# VRAM.net
KiCad netlist of a schematic drawn in Altium Designer
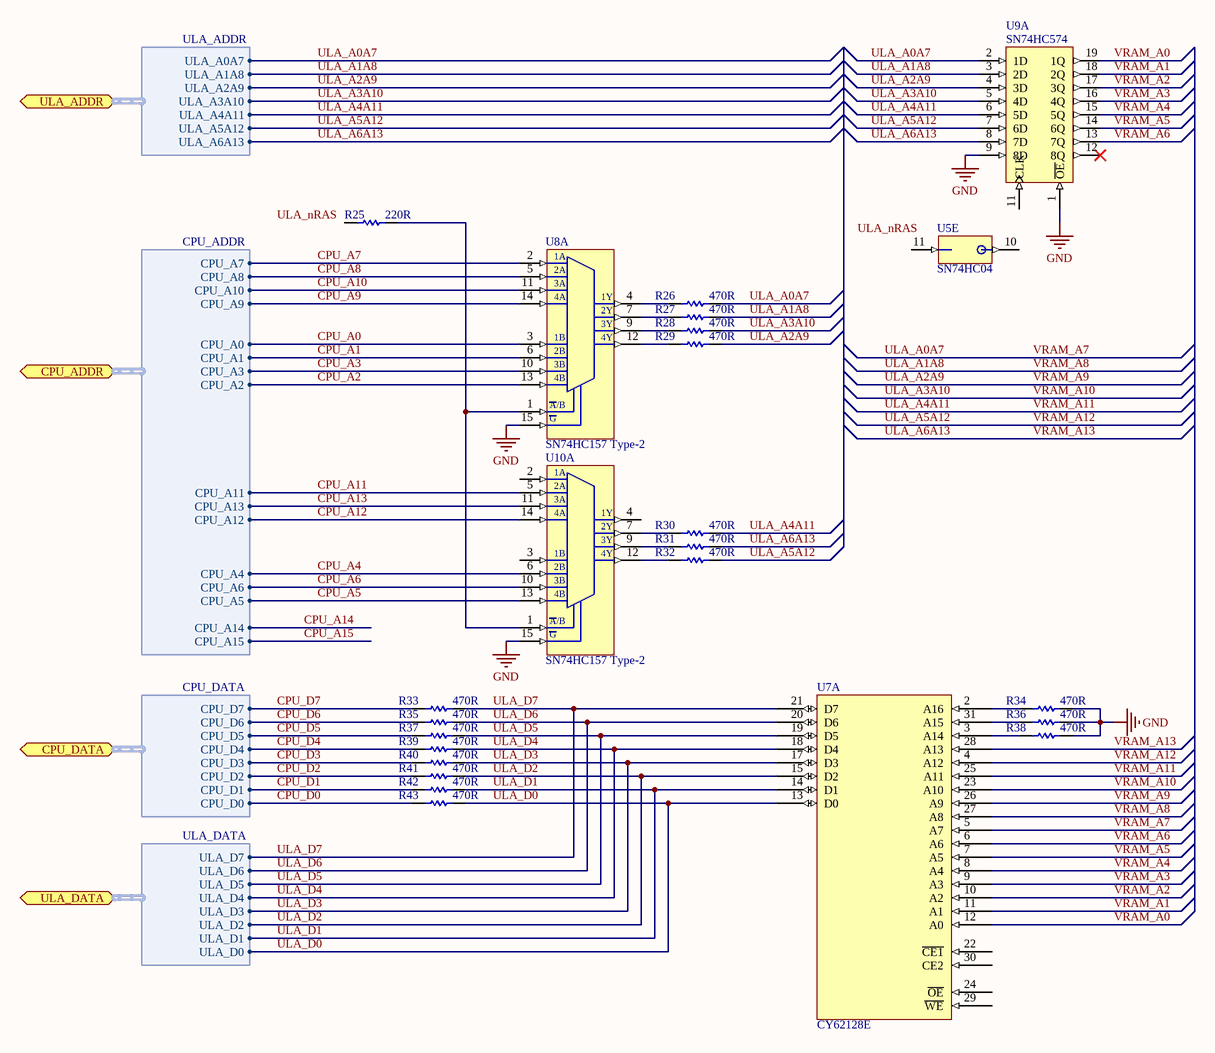
[diagram p0: VRAM.SchDoc]

(export (version "E")
  (design (tool "Eeschema 10.0.6"))
  (components
    (comp (ref "R25") (value "220R") (footprint "0805") (libsource (lib "Basic") (part "Resistor")))
    (comp (ref "R26") (value "470R") (footprint "0805") (libsource (lib "Basic") (part "Resistor")))
    (comp (ref "R27") (value "470R") (footprint "0805") (libsource (lib "Basic") (part "Resistor")))
    (comp (ref "R28") (value "470R") (footprint "0805") (libsource (lib "Basic") (part "Resistor")))
    (comp (ref "R29") (value "470R") (footprint "0805") (libsource (lib "Basic") (part "Resistor")))
    (comp (ref "R30") (value "470R") (footprint "0805") (libsource (lib "Basic") (part "Resistor")))
    (comp (ref "R31") (value "470R") (footprint "0805") (libsource (lib "Basic") (part "Resistor")))
    (comp (ref "R32") (value "470R") (footprint "0805") (libsource (lib "Basic") (part "Resistor")))
    (comp (ref "R33") (value "470R") (footprint "0805") (libsource (lib "Basic") (part "Resistor")))
    (comp (ref "R34") (value "470R") (footprint "0805") (libsource (lib "Basic") (part "Resistor")))
    (comp (ref "R35") (value "470R") (footprint "0805") (libsource (lib "Basic") (part "Resistor")))
    (comp (ref "R36") (value "470R") (footprint "0805") (libsource (lib "Basic") (part "Resistor")))
    (comp (ref "R37") (value "470R") (footprint "0805") (libsource (lib "Basic") (part "Resistor")))
    (comp (ref "R38") (value "470R") (footprint "0805") (libsource (lib "Basic") (part "Resistor")))
    (comp (ref "R39") (value "470R") (footprint "0805") (libsource (lib "Basic") (part "Resistor")))
    (comp (ref "R40") (value "470R") (footprint "0805") (libsource (lib "Basic") (part "Resistor")))
    (comp (ref "R41") (value "470R") (footprint "0805") (libsource (lib "Basic") (part "Resistor")))
    (comp (ref "R42") (value "470R") (footprint "0805") (libsource (lib "Basic") (part "Resistor")))
    (comp (ref "R43") (value "470R") (footprint "0805") (libsource (lib "Basic") (part "Resistor")))
    (comp (ref "U5")
      (value "SN74HC04")
      (footprint "SOIC14")
      (description "Hex Inverters")
      (libsource (lib "Texas Instruments") (part "SN74HC04"))
    )
    (comp (ref "U7")
      (value "CY62128E")
      (footprint "CY62128E-SOIC")
      (description "128KB Static RAM")
      (libsource (lib "Infineon") (part "CY62128E"))
    )
    (comp (ref "U8")
      (value "SN74HC157 Type-2")
      (footprint "TSSOP16")
      (description "Quadruple 2-Line To 1-Line Data Selectors/Mutiplexers")
      (libsource (lib "Texas Instruments") (part "SN74HC157 Type-2"))
    )
    (comp (ref "U9")
      (value "SN74HC574")
      (footprint "SOIC20")
      (description "Octal Edge-Triggered D-Type Flip-Flops With 3-State Outputs")
      (libsource (lib "Texas Instruments") (part "SN74HC574 Type-2"))
    )
    (comp (ref "U10")
      (value "SN74HC157 Type-2")
      (footprint "TSSOP16")
      (description "Quadruple 2-Line To 1-Line Data Selectors/Mutiplexers")
      (libsource (lib "Texas Instruments") (part "SN74HC157 Type-2"))
    )
  )
  (nets
    (net (code "5") (name "/CPU_A0") (class "Default")
      (node (ref "U8") (pin "3") (pinfunction "1B_3") (pintype "input"))
    )
    (net (code "6") (name "/CPU_A1") (class "Default")
      (node (ref "U8") (pin "6") (pinfunction "2B_6") (pintype "input"))
    )
    (net (code "7") (name "/CPU_A2") (class "Default")
      (node (ref "U8") (pin "13") (pinfunction "4B_13") (pintype "input"))
    )
    (net (code "8") (name "/CPU_A3") (class "Default")
      (node (ref "U8") (pin "10") (pinfunction "3B_10") (pintype "input"))
    )
    (net (code "9") (name "/CPU_A4") (class "Default")
      (node (ref "U10") (pin "6") (pinfunction "2B_6") (pintype "input"))
    )
    (net (code "10") (name "/CPU_A5") (class "Default")
      (node (ref "U10") (pin "13") (pinfunction "4B_13") (pintype "input"))
    )
    (net (code "11") (name "/CPU_A6") (class "Default")
      (node (ref "U10") (pin "10") (pinfunction "3B_10") (pintype "input"))
    )
    (net (code "12") (name "/CPU_A7") (class "Default")
      (node (ref "U8") (pin "2") (pinfunction "1A_2") (pintype "input"))
    )
    (net (code "13") (name "/CPU_A8") (class "Default")
      (node (ref "U8") (pin "5") (pinfunction "2A_5") (pintype "input"))
    )
    (net (code "14") (name "/CPU_A9") (class "Default")
      (node (ref "U8") (pin "14") (pinfunction "4A_14") (pintype "input"))
    )
    (net (code "15") (name "/CPU_A10") (class "Default")
      (node (ref "U8") (pin "11") (pinfunction "3A_11") (pintype "input"))
    )
    (net (code "16") (name "/CPU_A11") (class "Default")
      (node (ref "U10") (pin "5") (pinfunction "2A_5") (pintype "input"))
    )
    (net (code "17") (name "/CPU_A12") (class "Default")
      (node (ref "U10") (pin "14") (pinfunction "4A_14") (pintype "input"))
    )
    (net (code "18") (name "/CPU_A13") (class "Default")
      (node (ref "U10") (pin "11") (pinfunction "3A_11") (pintype "input"))
    )
    (net (code "21") (name "/CPU_D0") (class "Default")
      (node (ref "R43") (pin "2") (pinfunction "2_2") (pintype "passive"))
    )
    (net (code "22") (name "/CPU_D1") (class "Default")
      (node (ref "R42") (pin "2") (pinfunction "2_2") (pintype "passive"))
    )
    (net (code "23") (name "/CPU_D2") (class "Default")
      (node (ref "R41") (pin "2") (pinfunction "2_2") (pintype "passive"))
    )
    (net (code "24") (name "/CPU_D3") (class "Default")
      (node (ref "R40") (pin "2") (pinfunction "2_2") (pintype "passive"))
    )
    (net (code "25") (name "/CPU_D4") (class "Default")
      (node (ref "R39") (pin "2") (pinfunction "2_2") (pintype "passive"))
    )
    (net (code "26") (name "/CPU_D5") (class "Default")
      (node (ref "R37") (pin "2") (pinfunction "2_2") (pintype "passive"))
    )
    (net (code "27") (name "/CPU_D6") (class "Default")
      (node (ref "R35") (pin "2") (pinfunction "2_2") (pintype "passive"))
    )
    (net (code "28") (name "/CPU_D7") (class "Default")
      (node (ref "R33") (pin "2") (pinfunction "2_2") (pintype "passive"))
    )
    (net (code "29") (name "/ULA_A0A7") (class "Default")
      (node (ref "R26") (pin "1") (pinfunction "1_1") (pintype "passive"))
      (node (ref "U7") (pin "5") (pinfunction "A7_5") (pintype "input"))
      (node (ref "U9") (pin "2") (pinfunction "1D_2") (pintype "input"))
    )
    (net (code "30") (name "/ULA_A1A8") (class "Default")
      (node (ref "R27") (pin "1") (pinfunction "1_1") (pintype "passive"))
      (node (ref "U7") (pin "27") (pinfunction "A8_27") (pintype "input"))
      (node (ref "U9") (pin "3") (pinfunction "2D_3") (pintype "input"))
    )
    (net (code "31") (name "/ULA_A2A9") (class "Default")
      (node (ref "R29") (pin "1") (pinfunction "1_1") (pintype "passive"))
      (node (ref "U7") (pin "26") (pinfunction "A9_26") (pintype "input"))
      (node (ref "U9") (pin "4") (pinfunction "3D_4") (pintype "input"))
    )
    (net (code "32") (name "/ULA_A3A10") (class "Default")
      (node (ref "R28") (pin "1") (pinfunction "1_1") (pintype "passive"))
      (node (ref "U7") (pin "23") (pinfunction "A10_23") (pintype "input"))
      (node (ref "U9") (pin "5") (pinfunction "4D_5") (pintype "input"))
    )
    (net (code "33") (name "/ULA_A4A11") (class "Default")
      (node (ref "R30") (pin "1") (pinfunction "1_1") (pintype "passive"))
      (node (ref "U7") (pin "25") (pinfunction "A11_25") (pintype "input"))
      (node (ref "U9") (pin "6") (pinfunction "5D_6") (pintype "input"))
    )
    (net (code "34") (name "/ULA_A5A12") (class "Default")
      (node (ref "R32") (pin "1") (pinfunction "1_1") (pintype "passive"))
      (node (ref "U7") (pin "4") (pinfunction "A12_4") (pintype "input"))
      (node (ref "U9") (pin "7") (pinfunction "6D_7") (pintype "input"))
    )
    (net (code "35") (name "/ULA_A6A13") (class "Default")
      (node (ref "R31") (pin "1") (pinfunction "1_1") (pintype "passive"))
      (node (ref "U7") (pin "28") (pinfunction "A13_28") (pintype "input"))
      (node (ref "U9") (pin "8") (pinfunction "7D_8") (pintype "input"))
    )
    (net (code "36") (name "/ULA_D0") (class "Default")
      (node (ref "R43") (pin "1") (pinfunction "1_1") (pintype "passive"))
      (node (ref "U7") (pin "13") (pinfunction "D0_13") (pintype "bidirectional"))
    )
    (net (code "37") (name "/ULA_D1") (class "Default")
      (node (ref "R42") (pin "1") (pinfunction "1_1") (pintype "passive"))
      (node (ref "U7") (pin "14") (pinfunction "D1_14") (pintype "bidirectional"))
    )
    (net (code "38") (name "/ULA_D2") (class "Default")
      (node (ref "R41") (pin "1") (pinfunction "1_1") (pintype "passive"))
      (node (ref "U7") (pin "15") (pinfunction "D2_15") (pintype "bidirectional"))
    )
    (net (code "39") (name "/ULA_D3") (class "Default")
      (node (ref "R40") (pin "1") (pinfunction "1_1") (pintype "passive"))
      (node (ref "U7") (pin "17") (pinfunction "D3_17") (pintype "bidirectional"))
    )
    (net (code "40") (name "/ULA_D4") (class "Default")
      (node (ref "R39") (pin "1") (pinfunction "1_1") (pintype "passive"))
      (node (ref "U7") (pin "18") (pinfunction "D4_18") (pintype "bidirectional"))
    )
    (net (code "41") (name "/ULA_D5") (class "Default")
      (node (ref "R37") (pin "1") (pinfunction "1_1") (pintype "passive"))
      (node (ref "U7") (pin "19") (pinfunction "D5_19") (pintype "bidirectional"))
    )
    (net (code "42") (name "/ULA_D6") (class "Default")
      (node (ref "R35") (pin "1") (pinfunction "1_1") (pintype "passive"))
      (node (ref "U7") (pin "20") (pinfunction "D6_20") (pintype "bidirectional"))
    )
    (net (code "43") (name "/ULA_D7") (class "Default")
      (node (ref "R33") (pin "1") (pinfunction "1_1") (pintype "passive"))
      (node (ref "U7") (pin "21") (pinfunction "D7_21") (pintype "bidirectional"))
    )
    (net (code "45") (name "/VRAM_A0") (class "Default")
      (node (ref "U7") (pin "12") (pinfunction "A0_12") (pintype "input"))
      (node (ref "U9") (pin "19") (pinfunction "1Q_19") (pintype "output"))
    )
    (net (code "46") (name "/VRAM_A1") (class "Default")
      (node (ref "U7") (pin "11") (pinfunction "A1_11") (pintype "input"))
      (node (ref "U9") (pin "18") (pinfunction "2Q_18") (pintype "output"))
    )
    (net (code "47") (name "/VRAM_A2") (class "Default")
      (node (ref "U7") (pin "10") (pinfunction "A2_10") (pintype "input"))
      (node (ref "U9") (pin "17") (pinfunction "3Q_17") (pintype "output"))
    )
    (net (code "48") (name "/VRAM_A3") (class "Default")
      (node (ref "U7") (pin "9") (pinfunction "A3_9") (pintype "input"))
      (node (ref "U9") (pin "16") (pinfunction "4Q_16") (pintype "output"))
    )
    (net (code "49") (name "/VRAM_A4") (class "Default")
      (node (ref "U7") (pin "8") (pinfunction "A4_8") (pintype "input"))
      (node (ref "U9") (pin "15") (pinfunction "5Q_15") (pintype "output"))
    )
    (net (code "50") (name "/VRAM_A5") (class "Default")
      (node (ref "U7") (pin "7") (pinfunction "A5_7") (pintype "input"))
      (node (ref "U9") (pin "14") (pinfunction "6Q_14") (pintype "output"))
    )
    (net (code "51") (name "/VRAM_A6") (class "Default")
      (node (ref "U7") (pin "6") (pinfunction "A6_6") (pintype "input"))
      (node (ref "U9") (pin "13") (pinfunction "7Q_13") (pintype "output"))
    )
    (net (code "56") (name "GND") (class "Default")
      (node (ref "R34") (pin "1") (pinfunction "1_1") (pintype "passive"))
      (node (ref "R36") (pin "1") (pinfunction "1_1") (pintype "passive"))
      (node (ref "R38") (pin "1") (pinfunction "1_1") (pintype "passive"))
      (node (ref "U10") (pin "15") (pinfunction "G_15") (pintype "input"))
      (node (ref "U8") (pin "15") (pinfunction "G_15") (pintype "input"))
      (node (ref "U9") (pin "1") (pinfunction "~{OE}_1") (pintype "input"))
      (node (ref "U9") (pin "9") (pinfunction "8D_9") (pintype "input"))
    )
    (net (code "57") (name "Net-(U7A-A14)") (class "Default")
      (node (ref "R38") (pin "2") (pinfunction "2_2") (pintype "passive"))
      (node (ref "U7") (pin "3") (pinfunction "A14_3") (pintype "input"))
    )
    (net (code "58") (name "Net-(U7A-A15)") (class "Default")
      (node (ref "R36") (pin "2") (pinfunction "2_2") (pintype "passive"))
      (node (ref "U7") (pin "31") (pinfunction "A15_31") (pintype "input"))
    )
    (net (code "59") (name "Net-(U7A-A16)") (class "Default")
      (node (ref "R34") (pin "2") (pinfunction "2_2") (pintype "passive"))
      (node (ref "U7") (pin "2") (pinfunction "A16_2") (pintype "input"))
    )
    (net (code "60") (name "Net-(U8A-1Y)") (class "Default")
      (node (ref "R26") (pin "2") (pinfunction "2_2") (pintype "passive"))
      (node (ref "U8") (pin "4") (pinfunction "1Y_4") (pintype "output"))
    )
    (net (code "61") (name "Net-(U8A-2Y)") (class "Default")
      (node (ref "R27") (pin "2") (pinfunction "2_2") (pintype "passive"))
      (node (ref "U8") (pin "7") (pinfunction "2Y_7") (pintype "output"))
    )
    (net (code "62") (name "Net-(U8A-3Y)") (class "Default")
      (node (ref "R28") (pin "2") (pinfunction "2_2") (pintype "passive"))
      (node (ref "U8") (pin "9") (pinfunction "3Y_9") (pintype "output"))
    )
    (net (code "63") (name "Net-(U8A-4Y)") (class "Default")
      (node (ref "R29") (pin "2") (pinfunction "2_2") (pintype "passive"))
      (node (ref "U8") (pin "12") (pinfunction "4Y_12") (pintype "output"))
    )
    (net (code "64") (name "Net-(U10A-2Y)") (class "Default")
      (node (ref "R30") (pin "2") (pinfunction "2_2") (pintype "passive"))
      (node (ref "U10") (pin "7") (pinfunction "2Y_7") (pintype "output"))
    )
    (net (code "65") (name "Net-(U10A-3Y)") (class "Default")
      (node (ref "R31") (pin "2") (pinfunction "2_2") (pintype "passive"))
      (node (ref "U10") (pin "9") (pinfunction "3Y_9") (pintype "output"))
    )
    (net (code "66") (name "Net-(U10A-4Y)") (class "Default")
      (node (ref "R32") (pin "2") (pinfunction "2_2") (pintype "passive"))
      (node (ref "U10") (pin "12") (pinfunction "4Y_12") (pintype "output"))
    )
    (net (code "67") (name "Net-(U10A-A{slash}B)") (class "Default")
      (node (ref "R25") (pin "1") (pinfunction "1_1") (pintype "passive"))
      (node (ref "U10") (pin "1") (pinfunction "A/B_1") (pintype "input"))
      (node (ref "U8") (pin "1") (pinfunction "A/B_1") (pintype "input"))
    )
    (net (code "68") (name "unconnected-(R25-Pad2)") (class "Default")
      (node (ref "R25") (pin "2") (pinfunction "2_2") (pintype "passive"))
    )
    (net (code "69") (name "unconnected-(U5E-A-Pad11)") (class "Default")
      (node (ref "U5") (pin "11") (pinfunction "A_11") (pintype "input"))
    )
    (net (code "70") (name "unconnected-(U5E-Y-Pad10)") (class "Default")
      (node (ref "U5") (pin "10") (pinfunction "Y_10") (pintype "output"))
    )
    (net (code "71") (name "unconnected-(U7A-CE2-Pad30)") (class "Default")
      (node (ref "U7") (pin "30") (pinfunction "CE2_30") (pintype "input"))
    )
    (net (code "72") (name "unconnected-(U7A-~{CE1}-Pad22)") (class "Default")
      (node (ref "U7") (pin "22") (pinfunction "~{CE1}_22") (pintype "input"))
    )
    (net (code "73") (name "unconnected-(U7A-~{OE}-Pad24)") (class "Default")
      (node (ref "U7") (pin "24") (pinfunction "~{OE}_24") (pintype "input"))
    )
    (net (code "74") (name "unconnected-(U7A-~{WE}-Pad29)") (class "Default")
      (node (ref "U7") (pin "29") (pinfunction "~{WE}_29") (pintype "input"))
    )
    (net (code "75") (name "unconnected-(U9A-8Q-Pad12)") (class "Default")
      (node (ref "U9") (pin "12") (pinfunction "8Q_12") (pintype "output+no_connect"))
    )
    (net (code "76") (name "unconnected-(U9A-CLK-Pad11)") (class "Default")
      (node (ref "U9") (pin "11") (pinfunction "CLK_11") (pintype "input"))
    )
    (net (code "77") (name "unconnected-(U10A-1A-Pad2)") (class "Default")
      (node (ref "U10") (pin "2") (pinfunction "1A_2") (pintype "input"))
    )
    (net (code "78") (name "unconnected-(U10A-1B-Pad3)") (class "Default")
      (node (ref "U10") (pin "3") (pinfunction "1B_3") (pintype "input"))
    )
    (net (code "79") (name "unconnected-(U10A-1Y-Pad4)") (class "Default")
      (node (ref "U10") (pin "4") (pinfunction "1Y_4") (pintype "output"))
    )
  )
)
